# encoder.net
KiCad netlist of a schematic drawn in Altium Designer
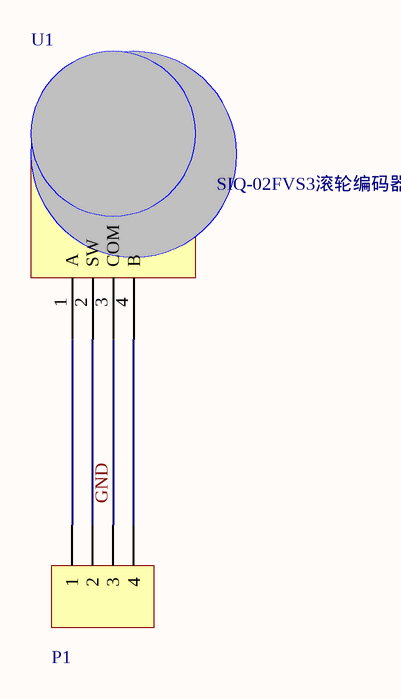
[diagram p0: encoder.SchDoc]

(export (version "E")
  (design (tool "Eeschema 10.0.6"))
  (components
    (comp (ref "P1")
      (value "~")
      (footprint "MX1.25-4P 卧")
      (description "Header, 4-Pin")
      (fields (field (name "PUBLISHER") "Altium Limited"))
      (libsource (lib "Miscellaneous Connectors") (part "Header 4"))
    )
    (comp (ref "U1")
      (value "SIQ-02FVS3滚轮编码器")
      (footprint "美上美SIQ-02FVS3滚轮编码器")
      (libsource (lib "zhjrm") (part "SIQ-02FVS3滚轮编码器"))
    )
  )
  (nets
    (net (code "1") (name "/GND") (class "Default")
      (node (ref "P1") (pin "3") (pinfunction "3_3") (pintype "passive"))
      (node (ref "U1") (pin "3") (pinfunction "COM_3") (pintype "passive"))
    )
    (net (code "2") (name "Net-(U1-A)") (class "Default")
      (node (ref "P1") (pin "1") (pinfunction "1_1") (pintype "passive"))
      (node (ref "U1") (pin "1") (pinfunction "A_1") (pintype "passive"))
    )
    (net (code "3") (name "Net-(U1-B)") (class "Default")
      (node (ref "P1") (pin "4") (pinfunction "4_4") (pintype "passive"))
      (node (ref "U1") (pin "4") (pinfunction "B_4") (pintype "passive"))
    )
    (net (code "4") (name "Net-(U1-SW)") (class "Default")
      (node (ref "P1") (pin "2") (pinfunction "2_2") (pintype "passive"))
      (node (ref "U1") (pin "2") (pinfunction "SW_2") (pintype "passive"))
    )
  )
)
